# quarz-pendler.net
KiCad netlist of a schematic drawn in EAGLE
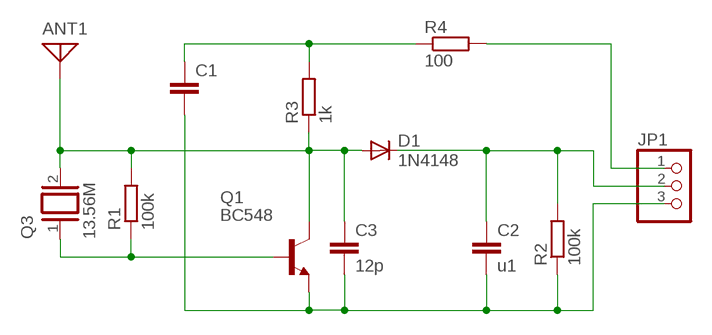
[diagram p0: schematic, sheet 1]

(export (version "E")
  (design (tool "Eeschema 10.0.6"))
  (components
    (comp (ref "ANT1")
      (value "ANTENNA")
      (footprint "eagle-import:PAD-01")
      (libsource (lib "eagle-import") (part "ANTENNA"))
    )
    (comp (ref "C1")
      (value "C-EU025-025X050")
      (footprint "eagle-import:C025-025X050")
      (libsource (lib "eagle-import") (part "C-EU025-025X050"))
    )
    (comp (ref "C2")
      (value "u1")
      (footprint "eagle-import:C025-025X050")
      (libsource (lib "eagle-import") (part "C-EU025-025X050"))
    )
    (comp (ref "C3")
      (value "12p")
      (footprint "eagle-import:C025-025X050")
      (libsource (lib "eagle-import") (part "C-EU025-025X050"))
    )
    (comp (ref "D1")
      (value "1N4148")
      (footprint "eagle-import:D-2.5")
      (libsource (lib "eagle-import") (part "DIODE-D-2.5"))
    )
    (comp (ref "JP1")
      (value "PINHD-1X3")
      (footprint "eagle-import:1X03")
      (libsource (lib "eagle-import") (part "PINHD-1X3"))
    )
    (comp (ref "Q1")
      (value "BC548")
      (footprint "eagle-import:TO92-EBC")
      (libsource (lib "eagle-import") (part "BC548"))
    )
    (comp (ref "Q3")
      (value "13.56M")
      (footprint "eagle-import:Q")
      (libsource (lib "eagle-import") (part "XTAL"))
    )
    (comp (ref "R1")
      (value "100k")
      (footprint "eagle-import:0207_2V")
      (libsource (lib "eagle-import") (part "R-EU_0207/2V"))
    )
    (comp (ref "R2")
      (value "100k")
      (footprint "eagle-import:0207_2V")
      (libsource (lib "eagle-import") (part "R-EU_0207/2V"))
    )
    (comp (ref "R3")
      (value "1k")
      (footprint "eagle-import:0207_2V")
      (libsource (lib "eagle-import") (part "R-EU_0207/2V"))
    )
    (comp (ref "R4")
      (value "100")
      (footprint "eagle-import:0207_2V")
      (libsource (lib "eagle-import") (part "R-EU_0207/2V"))
    )
  )
  (nets
    (net (code "1") (name "Net-(ANT1-Pad1)") (class "Default")
      (node (ref "ANT1") (pin "1") (pinfunction "1_1") (pintype "output"))
      (node (ref "C3") (pin "1") (pinfunction "1_1") (pintype "passive"))
      (node (ref "D1") (pin "A") (pinfunction "A_A") (pintype "passive"))
      (node (ref "Q1") (pin "C") (pinfunction "C_C") (pintype "passive"))
      (node (ref "Q3") (pin "2") (pinfunction "2_2") (pintype "passive"))
      (node (ref "R1") (pin "2") (pinfunction "2_2") (pintype "passive"))
      (node (ref "R3") (pin "1") (pinfunction "1_1") (pintype "passive"))
    )
    (net (code "2") (name "Net-(C1-Pad1)") (class "Default")
      (node (ref "C1") (pin "1") (pinfunction "1_1") (pintype "passive"))
      (node (ref "R3") (pin "2") (pinfunction "2_2") (pintype "passive"))
      (node (ref "R4") (pin "1") (pinfunction "1_1") (pintype "passive"))
    )
    (net (code "3") (name "Net-(C1-Pad2)") (class "Default")
      (node (ref "C1") (pin "2") (pinfunction "2_2") (pintype "passive"))
      (node (ref "C2") (pin "2") (pinfunction "2_2") (pintype "passive"))
      (node (ref "C3") (pin "2") (pinfunction "2_2") (pintype "passive"))
      (node (ref "JP1") (pin "3") (pinfunction "3_3") (pintype "passive"))
      (node (ref "Q1") (pin "E") (pinfunction "E_E") (pintype "passive"))
      (node (ref "R2") (pin "1") (pinfunction "1_1") (pintype "passive"))
    )
    (net (code "4") (name "Net-(C2-Pad1)") (class "Default")
      (node (ref "C2") (pin "1") (pinfunction "1_1") (pintype "passive"))
      (node (ref "D1") (pin "C") (pinfunction "C_C") (pintype "passive"))
      (node (ref "JP1") (pin "2") (pinfunction "2_2") (pintype "passive"))
      (node (ref "R2") (pin "2") (pinfunction "2_2") (pintype "passive"))
    )
    (net (code "5") (name "Net-(JP1-Pad1)") (class "Default")
      (node (ref "JP1") (pin "1") (pinfunction "1_1") (pintype "passive"))
      (node (ref "R4") (pin "2") (pinfunction "2_2") (pintype "passive"))
    )
    (net (code "6") (name "Net-(Q1-PadB)") (class "Default")
      (node (ref "Q1") (pin "B") (pinfunction "B_B") (pintype "passive"))
      (node (ref "Q3") (pin "1") (pinfunction "1_1") (pintype "passive"))
      (node (ref "R1") (pin "1") (pinfunction "1_1") (pintype "passive"))
    )
  )
)
